# AMRadio.net
KiCad netlist of a schematic drawn in Altium Designer
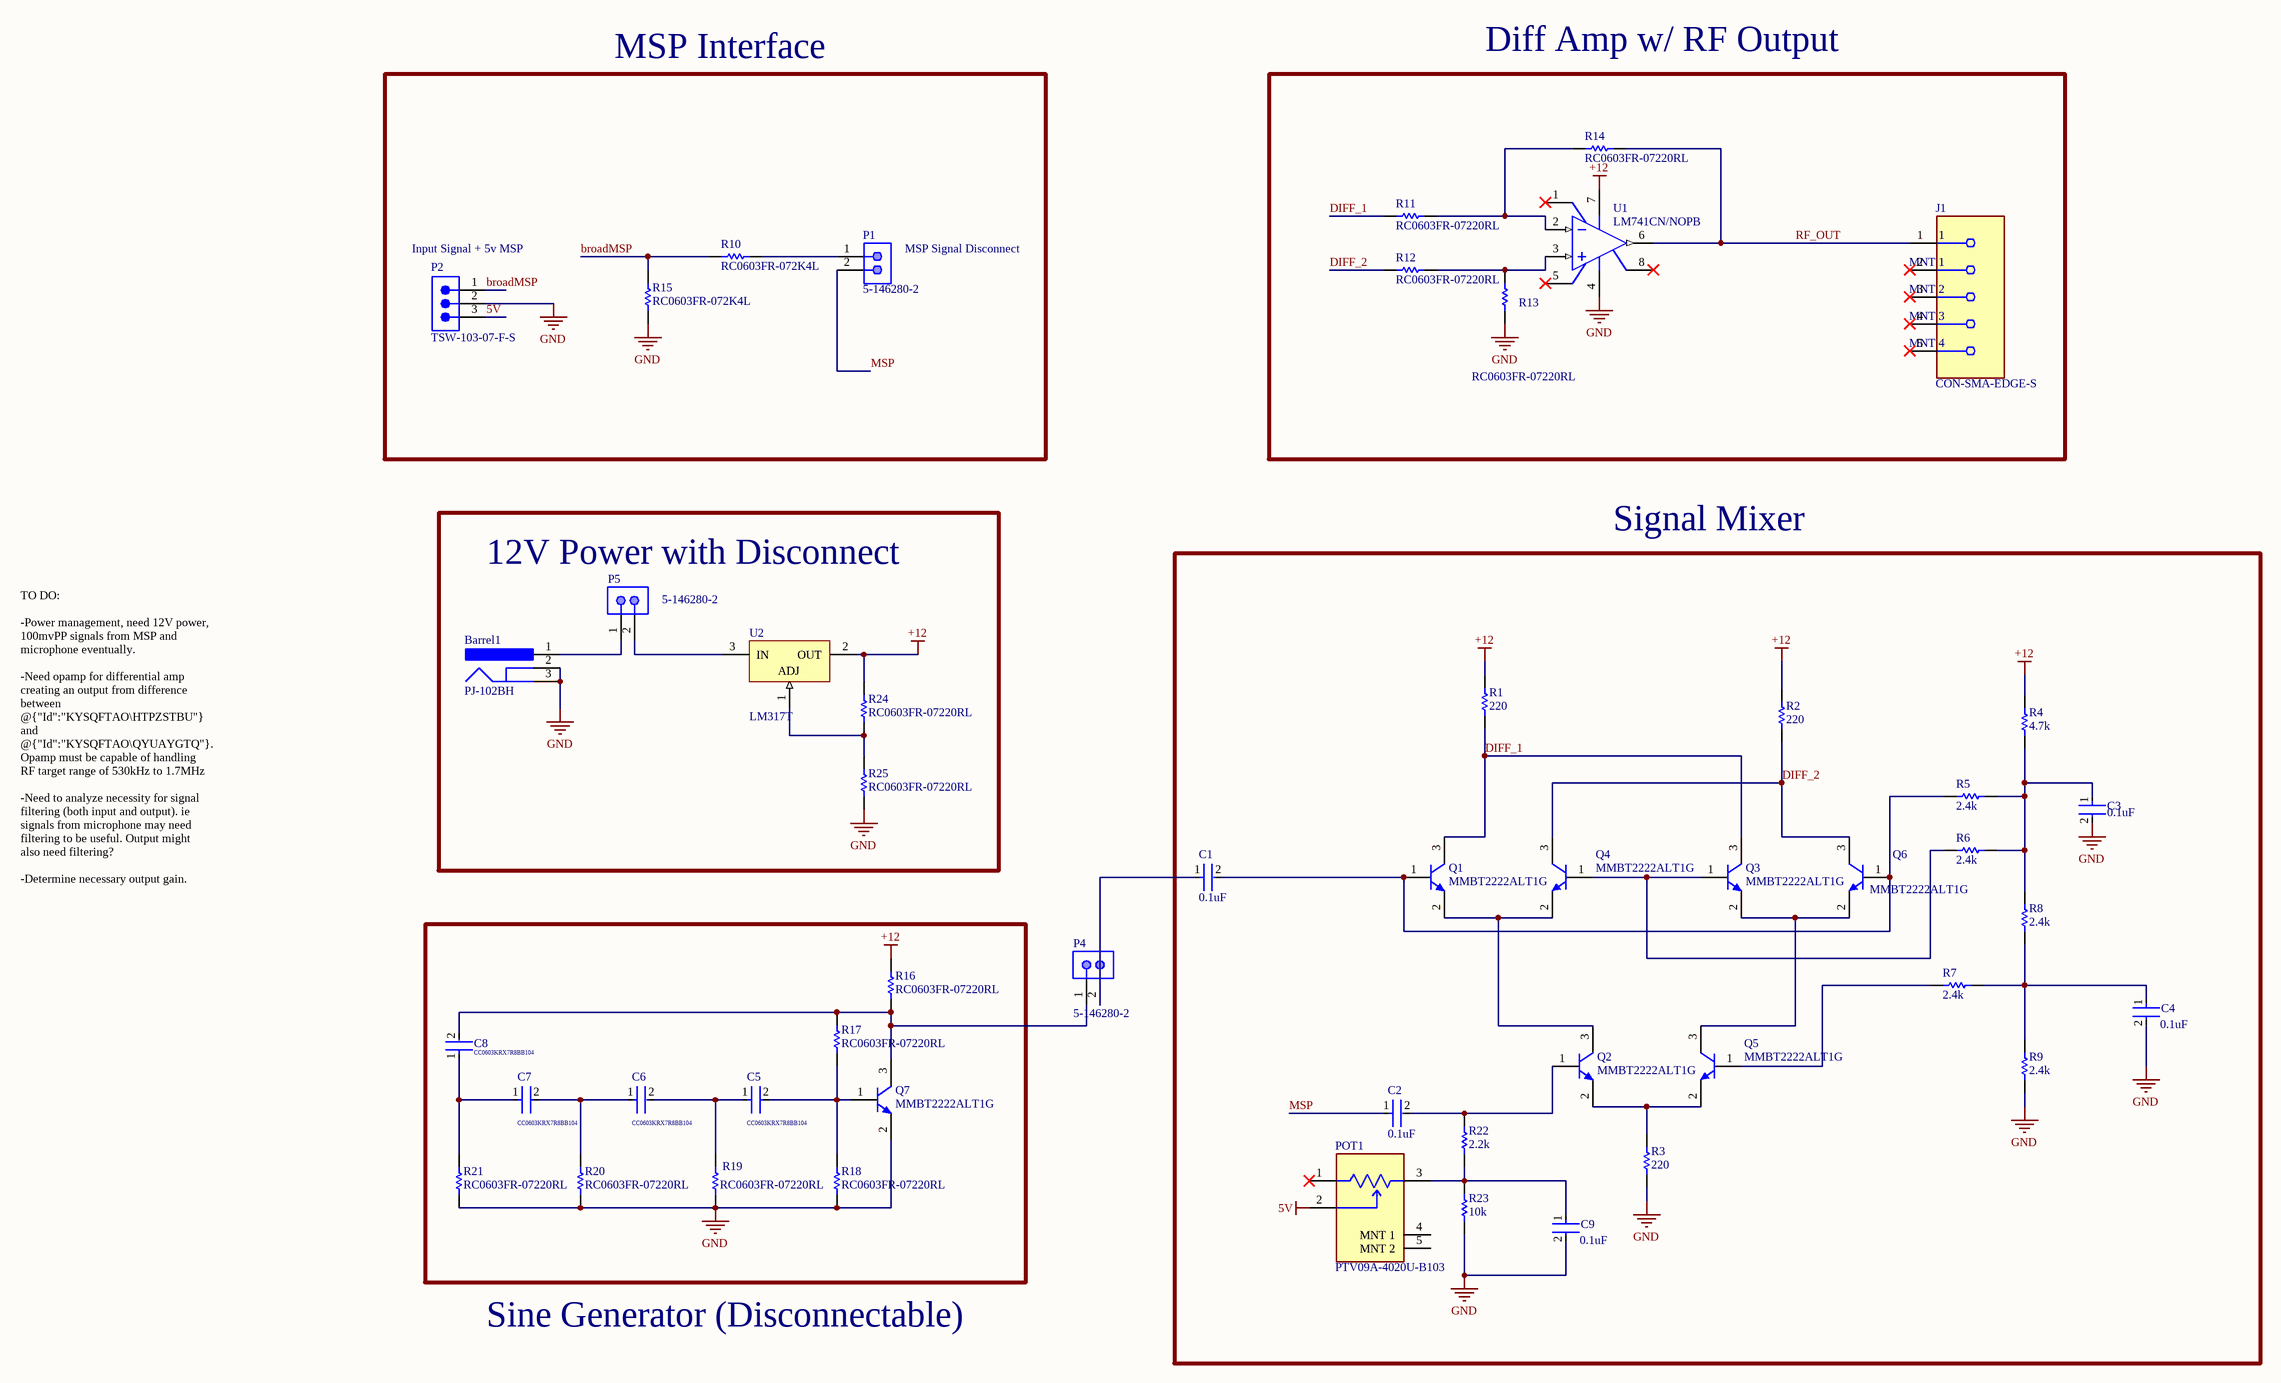
[diagram p0: AMRadio.SchDoc]

(export (version "E")
  (design (tool "Eeschema 10.0.6"))
  (components
    (comp (ref "Barrel1")
      (value "PJ-102BH")
      (footprint "CUI-PJ-102BH_V")
      (fields (field (name "MANUFACTURER") "CUIInc."))
      (libsource (lib "Altium Content Vault") (part "JACK-2CD3-RN"))
    )
    (comp (ref "C1")
      (value "0.1uF")
      (footprint "FP-CC0603-DA-MFG")
      (description "CAP CER 0.1UF 25V X7R 0603")
      (fields
        (field (name "MANUFACTURER") "YAGEO")
        (field (name "OCTOPART") "https://octopart.com/cc0603krx7r8bb104-yageo-8376534")
      )
      (libsource (lib "Altium Content Vault") (part "11868f565c42a9108669ba33697ecf6"))
    )
    (comp (ref "C2")
      (value "0.1uF")
      (footprint "FP-CC0603-DA-MFG")
      (description "CAP CER 0.1UF 25V X7R 0603")
      (fields
        (field (name "MANUFACTURER") "YAGEO")
        (field (name "OCTOPART") "https://octopart.com/cc0603krx7r8bb104-yageo-8376534")
      )
      (libsource (lib "Altium Content Vault") (part "11868f565c42a9108669ba33697ecf6"))
    )
    (comp (ref "C3")
      (value "0.1uF")
      (footprint "FP-CC0603-DA-MFG")
      (description "CAP CER 0.1UF 25V X7R 0603")
      (fields
        (field (name "MANUFACTURER") "YAGEO")
        (field (name "OCTOPART") "https://octopart.com/cc0603krx7r8bb104-yageo-8376534")
      )
      (libsource (lib "Altium Content Vault") (part "11868f565c42a9108669ba33697ecf6"))
    )
    (comp (ref "C4")
      (value "0.1uF")
      (footprint "FP-CC0603-DA-MFG")
      (description "CAP CER 0.1UF 25V X7R 0603")
      (fields
        (field (name "MANUFACTURER") "YAGEO")
        (field (name "OCTOPART") "https://octopart.com/cc0603krx7r8bb104-yageo-8376534")
      )
      (libsource (lib "Altium Content Vault") (part "11868f565c42a9108669ba33697ecf6"))
    )
    (comp (ref "C5")
      (value "CC0603KRX7R8BB104")
      (footprint "FP-CC0603-DA-MFG")
      (description "CAP CER 0.1UF 25V X7R 0603")
      (fields
        (field (name "MANUFACTURER") "YAGEO")
        (field (name "OCTOPART") "https://octopart.com/cc0603krx7r8bb104-yageo-8376534")
      )
      (libsource (lib "Altium Content Vault") (part "11868f565c42a9108669ba33697ecf6"))
    )
    (comp (ref "C6")
      (value "CC0603KRX7R8BB104")
      (footprint "FP-CC0603-DA-MFG")
      (description "CAP CER 0.1UF 25V X7R 0603")
      (fields
        (field (name "MANUFACTURER") "YAGEO")
        (field (name "OCTOPART") "https://octopart.com/cc0603krx7r8bb104-yageo-8376534")
      )
      (libsource (lib "Altium Content Vault") (part "11868f565c42a9108669ba33697ecf6"))
    )
    (comp (ref "C7")
      (value "CC0603KRX7R8BB104")
      (footprint "FP-CC0603-DA-MFG")
      (description "CAP CER 0.1UF 25V X7R 0603")
      (fields
        (field (name "MANUFACTURER") "YAGEO")
        (field (name "OCTOPART") "https://octopart.com/cc0603krx7r8bb104-yageo-8376534")
      )
      (libsource (lib "Altium Content Vault") (part "11868f565c42a9108669ba33697ecf6"))
    )
    (comp (ref "C8")
      (value "CC0603KRX7R8BB104")
      (footprint "FP-CC0603-DA-MFG")
      (description "CAP CER 0.1UF 25V X7R 0603")
      (fields
        (field (name "MANUFACTURER") "YAGEO")
        (field (name "OCTOPART") "https://octopart.com/cc0603krx7r8bb104-yageo-8376534")
      )
      (libsource (lib "Altium Content Vault") (part "11868f565c42a9108669ba33697ecf6"))
    )
    (comp (ref "C9")
      (value "0.1uF")
      (footprint "FP-CC0603-DA-MFG")
      (description "CAP CER 0.1UF 25V X7R 0603")
      (fields
        (field (name "MANUFACTURER") "YAGEO")
        (field (name "OCTOPART") "https://octopart.com/cc0603krx7r8bb104-yageo-8376534")
      )
      (libsource (lib "Altium Content Vault") (part "11868f565c42a9108669ba33697ecf6"))
    )
    (comp (ref "J1")
      (value "CON-SMA-EDGE-S")
      (footprint "FP-CON-SMA-EDGE-S-MFG")
      (description "CONN SMA JACK STR EDGE MNT")
      (fields
        (field (name "OCTOPART") "https://octopart.com/con-sma-edge-s-rf+solutions-70967450")
        (field (name "MANUFACTURER") "RF Solutions Ltd.")
      )
      (libsource (lib "Altium Content Vault") (part "a163d97a771fcdd2fd1f1a9264c171f"))
    )
    (comp (ref "P1")
      (value "5-146280-2")
      (footprint "TECO-5-146280-2_V")
      (fields (field (name "MANUFACTURER") "TE Connectivity"))
      (libsource (lib "Altium Content Vault") (part "CN-1P-M-R2"))
    )
    (comp (ref "P2")
      (value "TSW-103-07-F-S")
      (footprint "SMTC-TSW-103-07-X-S")
      (description "0.025\" SQ Post Header, Through-hole, Vertical, -55 to 125 degC, 2.54 mm Pitch, 3-Pin, Male, RoHS")
      (fields (field (name "MANUFACTURER") "Samtec"))
      (libsource (lib "Altium Content Vault") (part "SMTC-TSW-103-X-X-S-X"))
    )
    (comp (ref "P4")
      (value "5-146280-2")
      (footprint "TECO-5-146280-2_V")
      (fields (field (name "MANUFACTURER") "TE Connectivity"))
      (libsource (lib "") (part "CN-1P-M-R2_1"))
    )
    (comp (ref "P5")
      (value "5-146280-2")
      (footprint "TECO-5-146280-2_V")
      (fields (field (name "MANUFACTURER") "TE Connectivity"))
      (libsource (lib "") (part "CN-1P-M-R2_1"))
    )
    (comp (ref "POT1")
      (value "PTV09A-4020U-B103")
      (footprint "FP-PTV09A-4-MFG")
      (description "POT 10K OHM 1/20W CARBON LINEAR")
      (fields (field (name "TOLERANCE") "20%") (field (name "MANUFACTURER") "Bourns Inc."))
      (libsource (lib "Altium Content Vault") (part "3454c451b146ec4d4239c7813666f62"))
    )
    (comp (ref "Q1")
      (value "MMBT2222ALT1G")
      (footprint "ONSC-SOT-23-3-318-08_V")
      (description "General Purpose Transistor, NPN Silicon, 3-Pin SOT-23, Pb-Free, Tape and Reel")
      (fields (field (name "MANUFACTURER") "On Semiconductor"))
      (libsource (lib "Altium Content Vault") (part "ONSC-NPN-B1E2C3-3"))
    )
    (comp (ref "Q2")
      (value "MMBT2222ALT1G")
      (footprint "ONSC-SOT-23-3-318-08_V")
      (description "General Purpose Transistor, NPN Silicon, 3-Pin SOT-23, Pb-Free, Tape and Reel")
      (fields (field (name "MANUFACTURER") "On Semiconductor"))
      (libsource (lib "Altium Content Vault") (part "ONSC-NPN-B1E2C3-3"))
    )
    (comp (ref "Q3")
      (value "MMBT2222ALT1G")
      (footprint "ONSC-SOT-23-3-318-08_V")
      (description "General Purpose Transistor, NPN Silicon, 3-Pin SOT-23, Pb-Free, Tape and Reel")
      (fields (field (name "MANUFACTURER") "On Semiconductor"))
      (libsource (lib "Altium Content Vault") (part "ONSC-NPN-B1E2C3-3"))
    )
    (comp (ref "Q4")
      (value "MMBT2222ALT1G")
      (footprint "ONSC-SOT-23-3-318-08_V")
      (description "General Purpose Transistor, NPN Silicon, 3-Pin SOT-23, Pb-Free, Tape and Reel")
      (fields (field (name "MANUFACTURER") "On Semiconductor"))
      (libsource (lib "Altium Content Vault") (part "ONSC-NPN-B1E2C3-3"))
    )
    (comp (ref "Q5")
      (value "MMBT2222ALT1G")
      (footprint "ONSC-SOT-23-3-318-08_V")
      (description "General Purpose Transistor, NPN Silicon, 3-Pin SOT-23, Pb-Free, Tape and Reel")
      (fields (field (name "MANUFACTURER") "On Semiconductor"))
      (libsource (lib "Altium Content Vault") (part "ONSC-NPN-B1E2C3-3"))
    )
    (comp (ref "Q6")
      (value "MMBT2222ALT1G")
      (footprint "ONSC-SOT-23-3-318-08_V")
      (description "General Purpose Transistor, NPN Silicon, 3-Pin SOT-23, Pb-Free, Tape and Reel")
      (fields (field (name "MANUFACTURER") "On Semiconductor"))
      (libsource (lib "Altium Content Vault") (part "ONSC-NPN-B1E2C3-3"))
    )
    (comp (ref "Q7")
      (value "MMBT2222ALT1G")
      (footprint "ONSC-SOT-23-3-318-08_V")
      (description "General Purpose Transistor, NPN Silicon, 3-Pin SOT-23, Pb-Free, Tape and Reel")
      (fields (field (name "MANUFACTURER") "On Semiconductor"))
      (libsource (lib "Altium Content Vault") (part "ONSC-NPN-B1E2C3-3"))
    )
    (comp (ref "R1")
      (value "220")
      (footprint "RESC1608X55X25ML10T15")
      (libsource (lib "Altium Content Vault") (part "RES-2"))
    )
    (comp (ref "R2")
      (value "220")
      (footprint "RESC1608X55X25ML10T15")
      (libsource (lib "Altium Content Vault") (part "RES-2"))
    )
    (comp (ref "R3")
      (value "220")
      (footprint "RESC1608X55X25ML10T15")
      (libsource (lib "Altium Content Vault") (part "RES-2"))
    )
    (comp (ref "R4")
      (value "4.7k")
      (footprint "RESC1608X55X25LL10T15")
      (description "Chip Resistor, 4.7 kOhm, +/- 1%, 0.1 W, -55 to 155 degC, 0603 (1608 Metric), RoHS, Tape and Reel")
      (fields (field (name "MANUFACTURER") "Yageo") (field (name "TOLERANCE") "±1%"))
      (libsource (lib "Altium Content Vault") (part "RES-2"))
    )
    (comp (ref "R5")
      (value "2.4k")
      (footprint "RESC1608X55X25LL10T15")
      (description "Chip Resistor, 2.4 kOhm, +/- 1%, 0.1 W, -55 to 155 degC, 0603 (1608 Metric), RoHS, Tape and Reel")
      (fields (field (name "MANUFACTURER") "Yageo") (field (name "TOLERANCE") "±1%"))
      (libsource (lib "Altium Content Vault") (part "RES-2"))
    )
    (comp (ref "R6")
      (value "2.4k")
      (footprint "RESC1608X55X25LL10T15")
      (description "Chip Resistor, 2.4 kOhm, +/- 1%, 0.1 W, -55 to 155 degC, 0603 (1608 Metric), RoHS, Tape and Reel")
      (fields (field (name "MANUFACTURER") "Yageo") (field (name "TOLERANCE") "±1%"))
      (libsource (lib "Altium Content Vault") (part "RES-2"))
    )
    (comp (ref "R7")
      (value "2.4k")
      (footprint "RESC1608X55X25LL10T15")
      (description "Chip Resistor, 2.4 kOhm, +/- 1%, 0.1 W, -55 to 155 degC, 0603 (1608 Metric), RoHS, Tape and Reel")
      (fields (field (name "MANUFACTURER") "Yageo") (field (name "TOLERANCE") "±1%"))
      (libsource (lib "Altium Content Vault") (part "RES-2"))
    )
    (comp (ref "R8")
      (value "2.4k")
      (footprint "RESC1608X55X25LL10T15")
      (description "Chip Resistor, 2.4 kOhm, +/- 1%, 0.1 W, -55 to 155 degC, 0603 (1608 Metric), RoHS, Tape and Reel")
      (fields (field (name "MANUFACTURER") "Yageo") (field (name "TOLERANCE") "±1%"))
      (libsource (lib "Altium Content Vault") (part "RES-2"))
    )
    (comp (ref "R9")
      (value "2.4k")
      (footprint "RESC1608X55X25LL10T15")
      (description "Chip Resistor, 2.4 kOhm, +/- 1%, 0.1 W, -55 to 155 degC, 0603 (1608 Metric), RoHS, Tape and Reel")
      (fields (field (name "MANUFACTURER") "Yageo") (field (name "TOLERANCE") "±1%"))
      (libsource (lib "Altium Content Vault") (part "RES-2"))
    )
    (comp (ref "R10")
      (value "RC0603FR-072K4L")
      (footprint "RESC1608X55X25LL10T15")
      (description "Chip Resistor, 4.7 kOhm, +/- 1%, 0.1 W, -55 to 155 degC, 0603 (1608 Metric), RoHS, Tape and Reel")
      (fields (field (name "MANUFACTURER") "Yageo") (field (name "TOLERANCE") "±1%"))
      (libsource (lib "Altium Content Vault") (part "RES-2"))
    )
    (comp (ref "R11")
      (value "RC0603FR-07220RL")
      (footprint "RESC1608X55X25ML10T15")
      (libsource (lib "Altium Content Vault") (part "RES-2"))
    )
    (comp (ref "R12")
      (value "RC0603FR-07220RL")
      (footprint "RESC1608X55X25ML10T15")
      (libsource (lib "Altium Content Vault") (part "RES-2"))
    )
    (comp (ref "R13")
      (value "RC0603FR-07220RL")
      (footprint "RESC1608X55X25ML10T15")
      (libsource (lib "Altium Content Vault") (part "RES-2"))
    )
    (comp (ref "R14")
      (value "RC0603FR-07220RL")
      (footprint "RESC1608X55X25ML10T15")
      (libsource (lib "Altium Content Vault") (part "RES-2"))
    )
    (comp (ref "R15")
      (value "RC0603FR-072K4L")
      (footprint "RESC1608X55X25LL10T15")
      (description "Chip Resistor, 4.7 kOhm, +/- 1%, 0.1 W, -55 to 155 degC, 0603 (1608 Metric), RoHS, Tape and Reel")
      (fields (field (name "MANUFACTURER") "Yageo") (field (name "TOLERANCE") "±1%"))
      (libsource (lib "Altium Content Vault") (part "RES-2"))
    )
    (comp (ref "R16")
      (value "RC0603FR-07220RL")
      (footprint "RESC1608X55X25ML10T15")
      (libsource (lib "Altium Content Vault") (part "RES-2"))
    )
    (comp (ref "R17")
      (value "RC0603FR-07220RL")
      (footprint "RESC1608X55X25ML10T15")
      (libsource (lib "Altium Content Vault") (part "RES-2"))
    )
    (comp (ref "R18")
      (value "RC0603FR-07220RL")
      (footprint "RESC1608X55X25ML10T15")
      (libsource (lib "Altium Content Vault") (part "RES-2"))
    )
    (comp (ref "R19")
      (value "RC0603FR-07220RL")
      (footprint "RESC1608X55X25ML10T15")
      (libsource (lib "Altium Content Vault") (part "RES-2"))
    )
    (comp (ref "R20")
      (value "RC0603FR-07220RL")
      (footprint "RESC1608X55X25ML10T15")
      (libsource (lib "Altium Content Vault") (part "RES-2"))
    )
    (comp (ref "R21")
      (value "RC0603FR-07220RL")
      (footprint "RESC1608X55X25ML10T15")
      (libsource (lib "Altium Content Vault") (part "RES-2"))
    )
    (comp (ref "R22")
      (value "2.2k")
      (footprint "RESC1608X55X25ML10T15")
      (libsource (lib "Altium Content Vault") (part "RES-2"))
    )
    (comp (ref "R23")
      (value "10k")
      (footprint "RESC1608X55X25ML10T15")
      (libsource (lib "Altium Content Vault") (part "RES-2"))
    )
    (comp (ref "R24")
      (value "RC0603FR-07220RL")
      (footprint "RESC1608X55X25ML10T15")
      (libsource (lib "Altium Content Vault") (part "RES-2"))
    )
    (comp (ref "R25")
      (value "RC0603FR-07220RL")
      (footprint "RESC1608X55X25ML10T15")
      (libsource (lib "Altium Content Vault") (part "RES-2"))
    )
    (comp (ref "U1")
      (value "LM741CN/NOPB")
      (footprint "P0008A")
      (description "Operational Amplifier, 8-pin MDIP, Pb-Free")
      (fields (field (name "MANUFACTURER") "Texas Instruments"))
      (libsource (lib "Altium Content Vault") (part "AMP-OPA-LM741-8"))
    )
    (comp (ref "U2")
      (value "LM317T")
      (footprint "TO-220")
      (description "1.5A, 1.2V to 37V Adjustable Voltage Regulator, 3-Pin TO-220")
      (libsource (lib "Altium Content Vault") (part "PM-REG-117-SIL3"))
    )
  )
  (nets
    (net (code "1") (name "+12") (class "Default")
      (node (ref "R1") (pin "1") (pinfunction "1_1") (pintype "passive"))
      (node (ref "R16") (pin "1") (pinfunction "1_1") (pintype "passive"))
      (node (ref "R2") (pin "1") (pinfunction "1_1") (pintype "passive"))
      (node (ref "R24") (pin "1") (pinfunction "1_1") (pintype "passive"))
      (node (ref "R4") (pin "2") (pinfunction "2_2") (pintype "passive"))
      (node (ref "U1") (pin "7") (pinfunction "V+_7") (pintype "power_in"))
      (node (ref "U2") (pin "2") (pinfunction "OUT_2") (pintype "power_in"))
    )
    (net (code "2") (name "/DIFF_1") (class "Default")
      (node (ref "Q1") (pin "3") (pinfunction "C_3") (pintype "passive"))
      (node (ref "Q3") (pin "3") (pinfunction "C_3") (pintype "passive"))
      (node (ref "R1") (pin "2") (pinfunction "2_2") (pintype "passive"))
      (node (ref "R11") (pin "1") (pinfunction "1_1") (pintype "passive"))
    )
    (net (code "3") (name "/DIFF_2") (class "Default")
      (node (ref "Q4") (pin "3") (pinfunction "C_3") (pintype "passive"))
      (node (ref "Q6") (pin "3") (pinfunction "C_3") (pintype "passive"))
      (node (ref "R12") (pin "1") (pinfunction "1_1") (pintype "passive"))
      (node (ref "R2") (pin "2") (pinfunction "2_2") (pintype "passive"))
    )
    (net (code "4") (name "/MSP") (class "Default")
      (node (ref "C2") (pin "1") (pinfunction "1_1") (pintype "passive"))
      (node (ref "P1") (pin "2") (pinfunction "2_2") (pintype "passive"))
    )
    (net (code "5") (name "/RF_OUT") (class "Default")
      (node (ref "J1") (pin "1") (pinfunction "1_1") (pintype "passive"))
      (node (ref "R14") (pin "2") (pinfunction "2_2") (pintype "passive"))
      (node (ref "U1") (pin "6") (pinfunction "OUT_6") (pintype "output"))
    )
    (net (code "6") (name "/broadMSP") (class "Default")
      (node (ref "P2") (pin "1") (pinfunction "1_1") (pintype "passive"))
      (node (ref "R10") (pin "2") (pinfunction "2_2") (pintype "passive"))
      (node (ref "R15") (pin "2") (pinfunction "2_2") (pintype "passive"))
    )
    (net (code "7") (name "5V") (class "Default")
      (node (ref "P2") (pin "3") (pinfunction "3_3") (pintype "passive"))
      (node (ref "POT1") (pin "2") (pinfunction "2_2") (pintype "passive"))
    )
    (net (code "8") (name "GND") (class "Default")
      (node (ref "Barrel1") (pin "2") (pinfunction "2_2") (pintype "passive"))
      (node (ref "Barrel1") (pin "3") (pinfunction "3_3") (pintype "passive"))
      (node (ref "C3") (pin "2") (pinfunction "2_2") (pintype "passive"))
      (node (ref "C4") (pin "2") (pinfunction "2_2") (pintype "passive"))
      (node (ref "C9") (pin "2") (pinfunction "2_2") (pintype "passive"))
      (node (ref "P2") (pin "2") (pinfunction "2_2") (pintype "passive"))
      (node (ref "Q7") (pin "2") (pinfunction "E_2") (pintype "passive"))
      (node (ref "R13") (pin "2") (pinfunction "2_2") (pintype "passive"))
      (node (ref "R15") (pin "1") (pinfunction "1_1") (pintype "passive"))
      (node (ref "R18") (pin "2") (pinfunction "2_2") (pintype "passive"))
      (node (ref "R19") (pin "2") (pinfunction "2_2") (pintype "passive"))
      (node (ref "R20") (pin "2") (pinfunction "2_2") (pintype "passive"))
      (node (ref "R21") (pin "2") (pinfunction "2_2") (pintype "passive"))
      (node (ref "R23") (pin "2") (pinfunction "2_2") (pintype "passive"))
      (node (ref "R25") (pin "2") (pinfunction "2_2") (pintype "passive"))
      (node (ref "R3") (pin "2") (pinfunction "2_2") (pintype "passive"))
      (node (ref "R9") (pin "2") (pinfunction "2_2") (pintype "passive"))
      (node (ref "U1") (pin "4") (pinfunction "V-_4") (pintype "power_in"))
    )
    (net (code "9") (name "Net-(Barrel1-Pad1)") (class "Default")
      (node (ref "Barrel1") (pin "1") (pinfunction "1_1") (pintype "passive"))
      (node (ref "P5") (pin "1") (pinfunction "1_1") (pintype "passive"))
    )
    (net (code "10") (name "Net-(C1-Pad1)") (class "Default")
      (node (ref "C1") (pin "1") (pinfunction "1_1") (pintype "passive"))
      (node (ref "P4") (pin "2") (pinfunction "2_2") (pintype "passive"))
    )
    (net (code "11") (name "Net-(C3-Pad1)") (class "Default")
      (node (ref "C3") (pin "1") (pinfunction "1_1") (pintype "passive"))
      (node (ref "R4") (pin "1") (pinfunction "1_1") (pintype "passive"))
      (node (ref "R5") (pin "2") (pinfunction "2_2") (pintype "passive"))
      (node (ref "R6") (pin "2") (pinfunction "2_2") (pintype "passive"))
      (node (ref "R8") (pin "1") (pinfunction "1_1") (pintype "passive"))
    )
    (net (code "12") (name "Net-(C4-Pad1)") (class "Default")
      (node (ref "C4") (pin "1") (pinfunction "1_1") (pintype "passive"))
      (node (ref "R7") (pin "2") (pinfunction "2_2") (pintype "passive"))
      (node (ref "R8") (pin "2") (pinfunction "2_2") (pintype "passive"))
      (node (ref "R9") (pin "1") (pinfunction "1_1") (pintype "passive"))
    )
    (net (code "13") (name "Net-(C5-Pad1)") (class "Default")
      (node (ref "C5") (pin "1") (pinfunction "1_1") (pintype "passive"))
      (node (ref "C6") (pin "2") (pinfunction "2_2") (pintype "passive"))
      (node (ref "R19") (pin "1") (pinfunction "1_1") (pintype "passive"))
    )
    (net (code "14") (name "Net-(C6-Pad1)") (class "Default")
      (node (ref "C6") (pin "1") (pinfunction "1_1") (pintype "passive"))
      (node (ref "C7") (pin "2") (pinfunction "2_2") (pintype "passive"))
      (node (ref "R20") (pin "1") (pinfunction "1_1") (pintype "passive"))
    )
    (net (code "15") (name "Net-(C7-Pad1)") (class "Default")
      (node (ref "C7") (pin "1") (pinfunction "1_1") (pintype "passive"))
      (node (ref "C8") (pin "1") (pinfunction "1_1") (pintype "passive"))
      (node (ref "R21") (pin "1") (pinfunction "1_1") (pintype "passive"))
    )
    (net (code "16") (name "Net-(C9-Pad1)") (class "Default")
      (node (ref "C9") (pin "1") (pinfunction "1_1") (pintype "passive"))
      (node (ref "POT1") (pin "3") (pinfunction "3_3") (pintype "passive"))
      (node (ref "R22") (pin "2") (pinfunction "2_2") (pintype "passive"))
      (node (ref "R23") (pin "1") (pinfunction "1_1") (pintype "passive"))
    )
    (net (code "17") (name "Net-(P1-Pad1)") (class "Default")
      (node (ref "P1") (pin "1") (pinfunction "1_1") (pintype "passive"))
      (node (ref "R10") (pin "1") (pinfunction "1_1") (pintype "passive"))
    )
    (net (code "18") (name "Net-(Q1-B)") (class "Default")
      (node (ref "C1") (pin "2") (pinfunction "2_2") (pintype "passive"))
      (node (ref "Q1") (pin "1") (pinfunction "B_1") (pintype "passive"))
      (node (ref "Q6") (pin "1") (pinfunction "B_1") (pintype "passive"))
      (node (ref "R5") (pin "1") (pinfunction "1_1") (pintype "passive"))
    )
    (net (code "19") (name "Net-(Q1-E)") (class "Default")
      (node (ref "Q1") (pin "2") (pinfunction "E_2") (pintype "passive"))
      (node (ref "Q2") (pin "3") (pinfunction "C_3") (pintype "passive"))
      (node (ref "Q4") (pin "2") (pinfunction "E_2") (pintype "passive"))
    )
    (net (code "20") (name "Net-(Q2-B)") (class "Default")
      (node (ref "C2") (pin "2") (pinfunction "2_2") (pintype "passive"))
      (node (ref "Q2") (pin "1") (pinfunction "B_1") (pintype "passive"))
      (node (ref "R22") (pin "1") (pinfunction "1_1") (pintype "passive"))
    )
    (net (code "21") (name "Net-(Q2-E)") (class "Default")
      (node (ref "Q2") (pin "2") (pinfunction "E_2") (pintype "passive"))
      (node (ref "Q5") (pin "2") (pinfunction "E_2") (pintype "passive"))
      (node (ref "R3") (pin "1") (pinfunction "1_1") (pintype "passive"))
    )
    (net (code "22") (name "Net-(Q3-B)") (class "Default")
      (node (ref "Q3") (pin "1") (pinfunction "B_1") (pintype "passive"))
      (node (ref "Q4") (pin "1") (pinfunction "B_1") (pintype "passive"))
      (node (ref "R6") (pin "1") (pinfunction "1_1") (pintype "passive"))
    )
    (net (code "23") (name "Net-(Q3-E)") (class "Default")
      (node (ref "Q3") (pin "2") (pinfunction "E_2") (pintype "passive"))
      (node (ref "Q5") (pin "3") (pinfunction "C_3") (pintype "passive"))
      (node (ref "Q6") (pin "2") (pinfunction "E_2") (pintype "passive"))
    )
    (net (code "24") (name "Net-(Q5-B)") (class "Default")
      (node (ref "Q5") (pin "1") (pinfunction "B_1") (pintype "passive"))
      (node (ref "R7") (pin "1") (pinfunction "1_1") (pintype "passive"))
    )
    (net (code "25") (name "Net-(Q7-B)") (class "Default")
      (node (ref "C5") (pin "2") (pinfunction "2_2") (pintype "passive"))
      (node (ref "Q7") (pin "1") (pinfunction "B_1") (pintype "passive"))
      (node (ref "R17") (pin "2") (pinfunction "2_2") (pintype "passive"))
      (node (ref "R18") (pin "1") (pinfunction "1_1") (pintype "passive"))
    )
    (net (code "26") (name "Net-(Q7-C)") (class "Default")
      (node (ref "C8") (pin "2") (pinfunction "2_2") (pintype "passive"))
      (node (ref "P4") (pin "1") (pinfunction "1_1") (pintype "passive"))
      (node (ref "Q7") (pin "3") (pinfunction "C_3") (pintype "passive"))
      (node (ref "R16") (pin "2") (pinfunction "2_2") (pintype "passive"))
      (node (ref "R17") (pin "1") (pinfunction "1_1") (pintype "passive"))
    )
    (net (code "27") (name "Net-(U1-IN+)") (class "Default")
      (node (ref "R12") (pin "2") (pinfunction "2_2") (pintype "passive"))
      (node (ref "R13") (pin "1") (pinfunction "1_1") (pintype "passive"))
      (node (ref "U1") (pin "3") (pinfunction "IN+_3") (pintype "input"))
    )
    (net (code "28") (name "Net-(U1-IN-)") (class "Default")
      (node (ref "R11") (pin "2") (pinfunction "2_2") (pintype "passive"))
      (node (ref "R14") (pin "1") (pinfunction "1_1") (pintype "passive"))
      (node (ref "U1") (pin "2") (pinfunction "IN-_2") (pintype "input"))
    )
    (net (code "29") (name "Net-(U2-ADJ)") (class "Default")
      (node (ref "R24") (pin "2") (pinfunction "2_2") (pintype "passive"))
      (node (ref "R25") (pin "1") (pinfunction "1_1") (pintype "passive"))
      (node (ref "U2") (pin "1") (pinfunction "ADJ_1") (pintype "input"))
    )
    (net (code "30") (name "Net-(U2-IN)") (class "Default")
      (node (ref "P5") (pin "2") (pinfunction "2_2") (pintype "passive"))
      (node (ref "U2") (pin "3") (pinfunction "IN_3") (pintype "power_in"))
    )
    (net (code "31") (name "unconnected-(J1-MNT_1-Pad2)") (class "Default")
      (node (ref "J1") (pin "2") (pinfunction "MNT_1_2") (pintype "passive+no_connect"))
    )
    (net (code "32") (name "unconnected-(J1-MNT_2-Pad3)") (class "Default")
      (node (ref "J1") (pin "3") (pinfunction "MNT_2_3") (pintype "passive+no_connect"))
    )
    (net (code "33") (name "unconnected-(J1-MNT_3-Pad4)") (class "Default")
      (node (ref "J1") (pin "4") (pinfunction "MNT_3_4") (pintype "passive+no_connect"))
    )
    (net (code "34") (name "unconnected-(J1-MNT_4-Pad5)") (class "Default")
      (node (ref "J1") (pin "5") (pinfunction "MNT_4_5") (pintype "passive+no_connect"))
    )
    (net (code "35") (name "unconnected-(POT1-MNT_1-Pad4)") (class "Default")
      (node (ref "POT1") (pin "4") (pinfunction "MNT_1_4") (pintype "passive"))
    )
    (net (code "36") (name "unconnected-(POT1-MNT_2-Pad5)") (class "Default")
      (node (ref "POT1") (pin "5") (pinfunction "MNT_2_5") (pintype "passive"))
    )
    (net (code "37") (name "unconnected-(POT1-Pad1)") (class "Default")
      (node (ref "POT1") (pin "1") (pinfunction "1_1") (pintype "passive+no_connect"))
    )
    (net (code "38") (name "unconnected-(U1-NC-Pad8)") (class "Default")
      (node (ref "U1") (pin "8") (pinfunction "NC_8") (pintype "passive+no_connect"))
    )
    (net (code "39") (name "unconnected-(U1-OFS_NULL-Pad1)") (class "Default")
      (node (ref "U1") (pin "1") (pinfunction "OFS_NULL_1") (pintype "passive+no_connect"))
    )
    (net (code "40") (name "unconnected-(U1-OFS_NULL-Pad5)") (class "Default")
      (node (ref "U1") (pin "5") (pinfunction "OFS_NULL_5") (pintype "passive+no_connect"))
    )
  )
)
